# Connectors-DAC-Controllers.net
KiCad netlist of a schematic drawn in Altium Designer
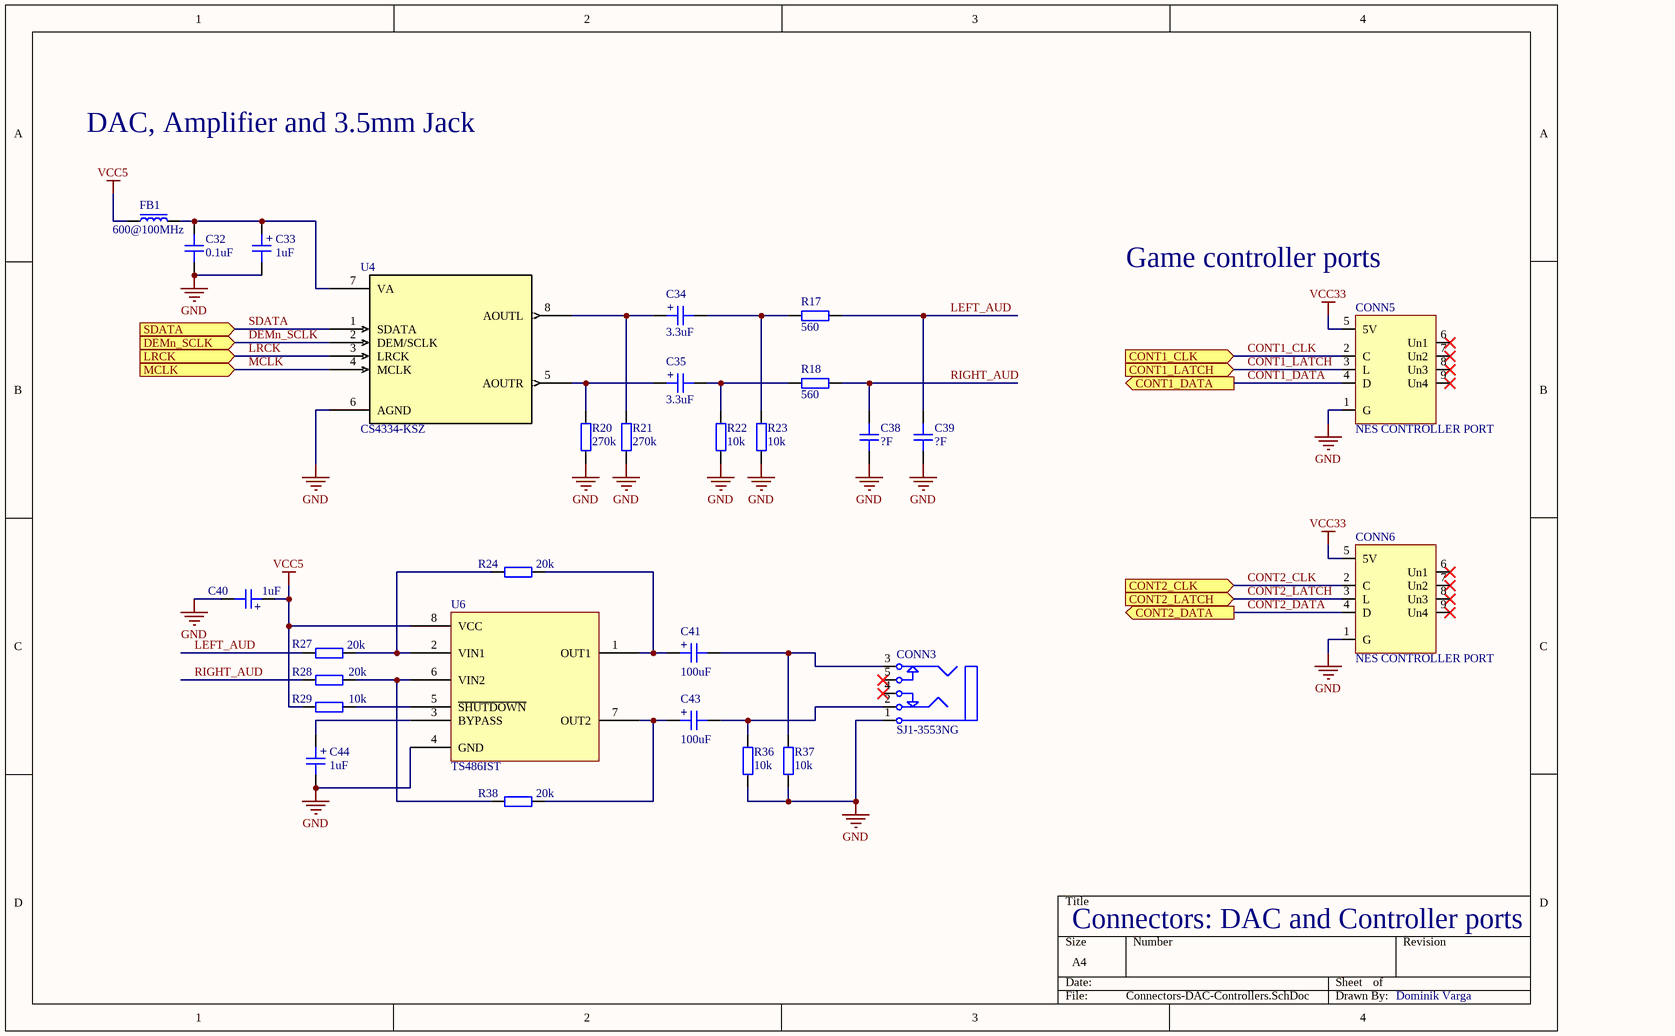
[diagram p0: Connectors-DAC-Controllers.SchDoc]

(export (version "E")
  (design (tool "Eeschema 10.0.6"))
  (components
    (comp (ref "C32")
      (value "0.1uF")
      (footprint "CAP_SMD0805")
      (description "Capacitor SMD 0805")
      (libsource (lib "NES-Components") (part "CAP_0805"))
    )
    (comp (ref "C33")
      (value "1uF")
      (footprint "CAPMP3216X180N")
      (description "Capacitor SMD Tantal A 16V")
      (libsource (lib "NES-Components") (part "CAP_ALEL_A"))
    )
    (comp (ref "C34")
      (value "3.3uF")
      (footprint "CAPMP3216X180N")
      (description "Capacitor SMD Tantal A 16V")
      (libsource (lib "NES-Components") (part "CAP_ALEL_A"))
    )
    (comp (ref "C35")
      (value "3.3uF")
      (footprint "CAPMP3216X180N")
      (description "Capacitor SMD Tantal A 16V")
      (libsource (lib "NES-Components") (part "CAP_ALEL_A"))
    )
    (comp (ref "C38")
      (value "?F")
      (footprint "CAP_SMD1206")
      (description "Capacitor SMD 1206 NP0 Dielektrikum")
      (libsource (lib "NES-Components") (part "CAP_1206"))
    )
    (comp (ref "C39")
      (value "?F")
      (footprint "CAP_SMD1206")
      (description "Capacitor SMD 1206 NP0 Dielektrikum")
      (libsource (lib "NES-Components") (part "CAP_1206"))
    )
    (comp (ref "C40")
      (value "1uF")
      (footprint "CAPMP3216X180N")
      (description "Capacitor SMD Tantal A 16V")
      (libsource (lib "NES-Components") (part "CAP_ALEL_A"))
    )
    (comp (ref "C41")
      (value "100uF")
      (footprint "CAPMP7343X310N")
      (description "Capacitor SMD Tantal D 20V")
      (libsource (lib "NES-Components") (part "CAP_ALEL_D"))
    )
    (comp (ref "C43")
      (value "100uF")
      (footprint "CAPMP7343X310N")
      (description "Capacitor SMD Tantal D 20V")
      (libsource (lib "NES-Components") (part "CAP_ALEL_D"))
    )
    (comp (ref "C44")
      (value "1uF")
      (footprint "CAPMP3216X180N")
      (description "Capacitor SMD Tantal A 16V")
      (libsource (lib "NES-Components") (part "CAP_ALEL_A"))
    )
    (comp (ref "CONN3")
      (value "SJ1-3553NG")
      (footprint "SJ1-3553NG")
      (description "CUI SJ1-3553NG 3.5mm jack receptacle")
      (fields (field (name "PUBLISHER") "Altium Limited"))
      (libsource (lib "NES-Components") (part "SJ1-3553NG"))
    )
    (comp (ref "CONN5")
      (value "NES CONTROLLER PORT")
      (footprint "NES controller port")
      (libsource (lib "NES-Components") (part "NES CONTROLLER PORT"))
    )
    (comp (ref "CONN6")
      (value "NES CONTROLLER PORT")
      (footprint "NES controller port")
      (libsource (lib "NES-Components") (part "NES CONTROLLER PORT"))
    )
    (comp (ref "FB1")
      (value "600@100MHz")
      (footprint "IND_SMD1206")
      (description "Ferrite Bead SMD 1206")
      (libsource (lib "NES-Components") (part "FB_1206"))
    )
    (comp (ref "R17")
      (value "560")
      (footprint "RES_SMD0603")
      (description "Resistor SMD 0603")
      (libsource (lib "NES-Components") (part "RES_0603"))
    )
    (comp (ref "R18")
      (value "560")
      (footprint "RES_SMD0603")
      (description "Resistor SMD 0603")
      (libsource (lib "NES-Components") (part "RES_0603"))
    )
    (comp (ref "R20")
      (value "270k")
      (footprint "RES_SMD0603")
      (description "Resistor SMD 0603")
      (libsource (lib "NES-Components") (part "RES_0603"))
    )
    (comp (ref "R21")
      (value "270k")
      (footprint "RES_SMD0603")
      (description "Resistor SMD 0603")
      (libsource (lib "NES-Components") (part "RES_0603"))
    )
    (comp (ref "R22")
      (value "10k")
      (footprint "RES_SMD0603")
      (description "Resistor SMD 0603")
      (libsource (lib "NES-Components") (part "RES_0603"))
    )
    (comp (ref "R23")
      (value "10k")
      (footprint "RES_SMD0603")
      (description "Resistor SMD 0603")
      (libsource (lib "NES-Components") (part "RES_0603"))
    )
    (comp (ref "R24")
      (value "20k")
      (footprint "RES_SMD0603")
      (description "Resistor SMD 0603")
      (libsource (lib "NES-Components") (part "RES_0603"))
    )
    (comp (ref "R27")
      (value "20k")
      (footprint "RES_SMD0603")
      (description "Resistor SMD 0603")
      (libsource (lib "NES-Components") (part "RES_0603"))
    )
    (comp (ref "R28")
      (value "20k")
      (footprint "RES_SMD0603")
      (description "Resistor SMD 0603")
      (libsource (lib "NES-Components") (part "RES_0603"))
    )
    (comp (ref "R29")
      (value "10k")
      (footprint "RES_SMD0603")
      (description "Resistor SMD 0603")
      (libsource (lib "NES-Components") (part "RES_0603"))
    )
    (comp (ref "R36")
      (value "10k")
      (footprint "RES_SMD0603")
      (description "Resistor SMD 0603")
      (libsource (lib "NES-Components") (part "RES_0603"))
    )
    (comp (ref "R37")
      (value "10k")
      (footprint "RES_SMD0603")
      (description "Resistor SMD 0603")
      (libsource (lib "NES-Components") (part "RES_0603"))
    )
    (comp (ref "R38")
      (value "20k")
      (footprint "RES_SMD0603")
      (description "Resistor SMD 0603")
      (libsource (lib "NES-Components") (part "RES_0603"))
    )
    (comp (ref "U4")
      (value "CS4334-KSZ")
      (footprint "SOIC127P600X175-8N")
      (description "DAC 2-CH Delta-Sigma 24-bit 8-Pin SOIC")
      (fields (field (name "COPYRIGHT") "Copyright (C) 2023 Ultra Librarian. All rights reserved."))
      (libsource (lib "NES-Components") (part "CS4334-KSZ"))
    )
    (comp (ref "U6")
      (value "TS486IST")
      (footprint "SOP65P490X109-8N")
      (description "100mW STEREO HEADPHONE AMPLIFIER WITH STANDBY\r\nMODE")
      (libsource (lib "NES-Components") (part "TS486IST"))
    )
  )
  (nets
    (net (code "1") (name "/CONT1_CLK") (class "Default")
      (node (ref "CONN5") (pin "2") (pinfunction "C_2") (pintype "passive"))
    )
    (net (code "2") (name "/CONT1_DATA") (class "Default")
      (node (ref "CONN5") (pin "4") (pinfunction "D_4") (pintype "passive"))
    )
    (net (code "3") (name "/CONT1_LATCH") (class "Default")
      (node (ref "CONN5") (pin "3") (pinfunction "L_3") (pintype "passive"))
    )
    (net (code "4") (name "/CONT2_CLK") (class "Default")
      (node (ref "CONN6") (pin "2") (pinfunction "C_2") (pintype "passive"))
    )
    (net (code "5") (name "/CONT2_DATA") (class "Default")
      (node (ref "CONN6") (pin "4") (pinfunction "D_4") (pintype "passive"))
    )
    (net (code "6") (name "/CONT2_LATCH") (class "Default")
      (node (ref "CONN6") (pin "3") (pinfunction "L_3") (pintype "passive"))
    )
    (net (code "7") (name "/DEMn_SCLK") (class "Default")
      (node (ref "U4") (pin "2") (pinfunction "DEM/SCLK_2") (pintype "input"))
    )
    (net (code "8") (name "/LEFT_AUD") (class "Default")
      (node (ref "C39") (pin "2") (pinfunction "2_2") (pintype "passive"))
      (node (ref "R17") (pin "2") (pinfunction "2_2") (pintype "passive"))
      (node (ref "R27") (pin "1") (pinfunction "1_1") (pintype "passive"))
    )
    (net (code "9") (name "/LRCK") (class "Default")
      (node (ref "U4") (pin "3") (pinfunction "LRCK_3") (pintype "input"))
    )
    (net (code "10") (name "/MCLK") (class "Default")
      (node (ref "U4") (pin "4") (pinfunction "MCLK_4") (pintype "input"))
    )
    (net (code "11") (name "/RIGHT_AUD") (class "Default")
      (node (ref "C38") (pin "2") (pinfunction "2_2") (pintype "passive"))
      (node (ref "R18") (pin "2") (pinfunction "2_2") (pintype "passive"))
      (node (ref "R28") (pin "1") (pinfunction "1_1") (pintype "passive"))
    )
    (net (code "12") (name "/SDATA") (class "Default")
      (node (ref "U4") (pin "1") (pinfunction "SDATA_1") (pintype "input"))
    )
    (net (code "13") (name "GND") (class "Default")
      (node (ref "C32") (pin "1") (pinfunction "1_1") (pintype "passive"))
      (node (ref "C33") (pin "2") (pinfunction "2_2") (pintype "passive"))
      (node (ref "C38") (pin "1") (pinfunction "1_1") (pintype "passive"))
      (node (ref "C39") (pin "1") (pinfunction "1_1") (pintype "passive"))
      (node (ref "C40") (pin "2") (pinfunction "2_2") (pintype "passive"))
      (node (ref "C44") (pin "2") (pinfunction "2_2") (pintype "passive"))
      (node (ref "CONN3") (pin "1") (pinfunction "1_1") (pintype "passive"))
      (node (ref "CONN5") (pin "1") (pinfunction "G_1") (pintype "passive"))
      (node (ref "CONN6") (pin "1") (pinfunction "G_1") (pintype "passive"))
      (node (ref "R20") (pin "2") (pinfunction "2_2") (pintype "passive"))
      (node (ref "R21") (pin "2") (pinfunction "2_2") (pintype "passive"))
      (node (ref "R22") (pin "2") (pinfunction "2_2") (pintype "passive"))
      (node (ref "R23") (pin "2") (pinfunction "2_2") (pintype "passive"))
      (node (ref "R36") (pin "1") (pinfunction "1_1") (pintype "passive"))
      (node (ref "R37") (pin "1") (pinfunction "1_1") (pintype "passive"))
      (node (ref "U4") (pin "6") (pinfunction "AGND_6") (pintype "power_in"))
      (node (ref "U6") (pin "4") (pinfunction "GND_4") (pintype "passive"))
    )
    (net (code "14") (name "Net-(C34-Pad2)") (class "Default")
      (node (ref "C34") (pin "2") (pinfunction "2_2") (pintype "passive"))
      (node (ref "R17") (pin "1") (pinfunction "1_1") (pintype "passive"))
      (node (ref "R23") (pin "1") (pinfunction "1_1") (pintype "passive"))
    )
    (net (code "15") (name "Net-(C35-Pad2)") (class "Default")
      (node (ref "C35") (pin "2") (pinfunction "2_2") (pintype "passive"))
      (node (ref "R18") (pin "1") (pinfunction "1_1") (pintype "passive"))
      (node (ref "R22") (pin "1") (pinfunction "1_1") (pintype "passive"))
    )
    (net (code "16") (name "Net-(C41-Pad2)") (class "Default")
      (node (ref "C41") (pin "2") (pinfunction "2_2") (pintype "passive"))
      (node (ref "CONN3") (pin "3") (pinfunction "3_3") (pintype "passive"))
      (node (ref "R37") (pin "2") (pinfunction "2_2") (pintype "passive"))
    )
    (net (code "17") (name "Net-(C43-Pad2)") (class "Default")
      (node (ref "C43") (pin "2") (pinfunction "2_2") (pintype "passive"))
      (node (ref "CONN3") (pin "2") (pinfunction "2_2") (pintype "passive"))
      (node (ref "R36") (pin "2") (pinfunction "2_2") (pintype "passive"))
    )
    (net (code "18") (name "Net-(U4-AOUTL)") (class "Default")
      (node (ref "C34") (pin "1") (pinfunction "1_1") (pintype "passive"))
      (node (ref "R21") (pin "1") (pinfunction "1_1") (pintype "passive"))
      (node (ref "U4") (pin "8") (pinfunction "AOUTL_8") (pintype "output"))
    )
    (net (code "19") (name "Net-(U4-AOUTR)") (class "Default")
      (node (ref "C35") (pin "1") (pinfunction "1_1") (pintype "passive"))
      (node (ref "R20") (pin "1") (pinfunction "1_1") (pintype "passive"))
      (node (ref "U4") (pin "5") (pinfunction "AOUTR_5") (pintype "output"))
    )
    (net (code "20") (name "Net-(U4-VA)") (class "Default")
      (node (ref "C32") (pin "2") (pinfunction "2_2") (pintype "passive"))
      (node (ref "C33") (pin "1") (pinfunction "1_1") (pintype "passive"))
      (node (ref "FB1") (pin "2") (pinfunction "2_2") (pintype "passive"))
      (node (ref "U4") (pin "7") (pinfunction "VA_7") (pintype "power_in"))
    )
    (net (code "21") (name "Net-(U6-BYPASS)") (class "Default")
      (node (ref "C44") (pin "1") (pinfunction "1_1") (pintype "passive"))
      (node (ref "U6") (pin "3") (pinfunction "BYPASS_3") (pintype "passive"))
    )
    (net (code "22") (name "Net-(U6-OUT1)") (class "Default")
      (node (ref "C41") (pin "1") (pinfunction "1_1") (pintype "passive"))
      (node (ref "R24") (pin "2") (pinfunction "2_2") (pintype "passive"))
      (node (ref "U6") (pin "1") (pinfunction "OUT1_1") (pintype "passive"))
    )
    (net (code "23") (name "Net-(U6-OUT2)") (class "Default")
      (node (ref "C43") (pin "1") (pinfunction "1_1") (pintype "passive"))
      (node (ref "R38") (pin "2") (pinfunction "2_2") (pintype "passive"))
      (node (ref "U6") (pin "7") (pinfunction "OUT2_7") (pintype "passive"))
    )
    (net (code "24") (name "Net-(U6-VIN1)") (class "Default")
      (node (ref "R24") (pin "1") (pinfunction "1_1") (pintype "passive"))
      (node (ref "R27") (pin "2") (pinfunction "2_2") (pintype "passive"))
      (node (ref "U6") (pin "2") (pinfunction "VIN1_2") (pintype "passive"))
    )
    (net (code "25") (name "Net-(U6-VIN2)") (class "Default")
      (node (ref "R28") (pin "2") (pinfunction "2_2") (pintype "passive"))
      (node (ref "R38") (pin "1") (pinfunction "1_1") (pintype "passive"))
      (node (ref "U6") (pin "6") (pinfunction "VIN2_6") (pintype "passive"))
    )
    (net (code "26") (name "Net-(U6-~{SHUTDOWN})") (class "Default")
      (node (ref "R29") (pin "2") (pinfunction "2_2") (pintype "passive"))
      (node (ref "U6") (pin "5") (pinfunction "~{SHUTDOWN}_5") (pintype "passive"))
    )
    (net (code "27") (name "VCC5") (class "Default")
      (node (ref "C40") (pin "1") (pinfunction "1_1") (pintype "passive"))
      (node (ref "FB1") (pin "1") (pinfunction "1_1") (pintype "passive"))
      (node (ref "R29") (pin "1") (pinfunction "1_1") (pintype "passive"))
      (node (ref "U6") (pin "8") (pinfunction "VCC_8") (pintype "passive"))
    )
    (net (code "28") (name "VCC33") (class "Default")
      (node (ref "CONN5") (pin "5") (pinfunction "5V_5") (pintype "passive"))
      (node (ref "CONN6") (pin "5") (pinfunction "5V_5") (pintype "passive"))
    )
    (net (code "29") (name "unconnected-(CONN3-Pad4)") (class "Default")
      (node (ref "CONN3") (pin "4") (pinfunction "4_4") (pintype "passive+no_connect"))
    )
    (net (code "30") (name "unconnected-(CONN3-Pad5)") (class "Default")
      (node (ref "CONN3") (pin "5") (pinfunction "5_5") (pintype "passive+no_connect"))
    )
    (net (code "31") (name "unconnected-(CONN5-Un1-Pad6)") (class "Default")
      (node (ref "CONN5") (pin "6") (pinfunction "Un1_6") (pintype "passive+no_connect"))
    )
    (net (code "32") (name "unconnected-(CONN5-Un2-Pad7)") (class "Default")
      (node (ref "CONN5") (pin "7") (pinfunction "Un2_7") (pintype "passive+no_connect"))
    )
    (net (code "33") (name "unconnected-(CONN5-Un3-Pad8)") (class "Default")
      (node (ref "CONN5") (pin "8") (pinfunction "Un3_8") (pintype "passive+no_connect"))
    )
    (net (code "34") (name "unconnected-(CONN5-Un4-Pad9)") (class "Default")
      (node (ref "CONN5") (pin "9") (pinfunction "Un4_9") (pintype "passive+no_connect"))
    )
    (net (code "35") (name "unconnected-(CONN6-Un1-Pad6)") (class "Default")
      (node (ref "CONN6") (pin "6") (pinfunction "Un1_6") (pintype "passive+no_connect"))
    )
    (net (code "36") (name "unconnected-(CONN6-Un2-Pad7)") (class "Default")
      (node (ref "CONN6") (pin "7") (pinfunction "Un2_7") (pintype "passive+no_connect"))
    )
    (net (code "37") (name "unconnected-(CONN6-Un3-Pad8)") (class "Default")
      (node (ref "CONN6") (pin "8") (pinfunction "Un3_8") (pintype "passive+no_connect"))
    )
    (net (code "38") (name "unconnected-(CONN6-Un4-Pad9)") (class "Default")
      (node (ref "CONN6") (pin "9") (pinfunction "Un4_9") (pintype "passive+no_connect"))
    )
  )
)
